# Ranger_I2C.net
KiCad netlist of a schematic drawn in EAGLE
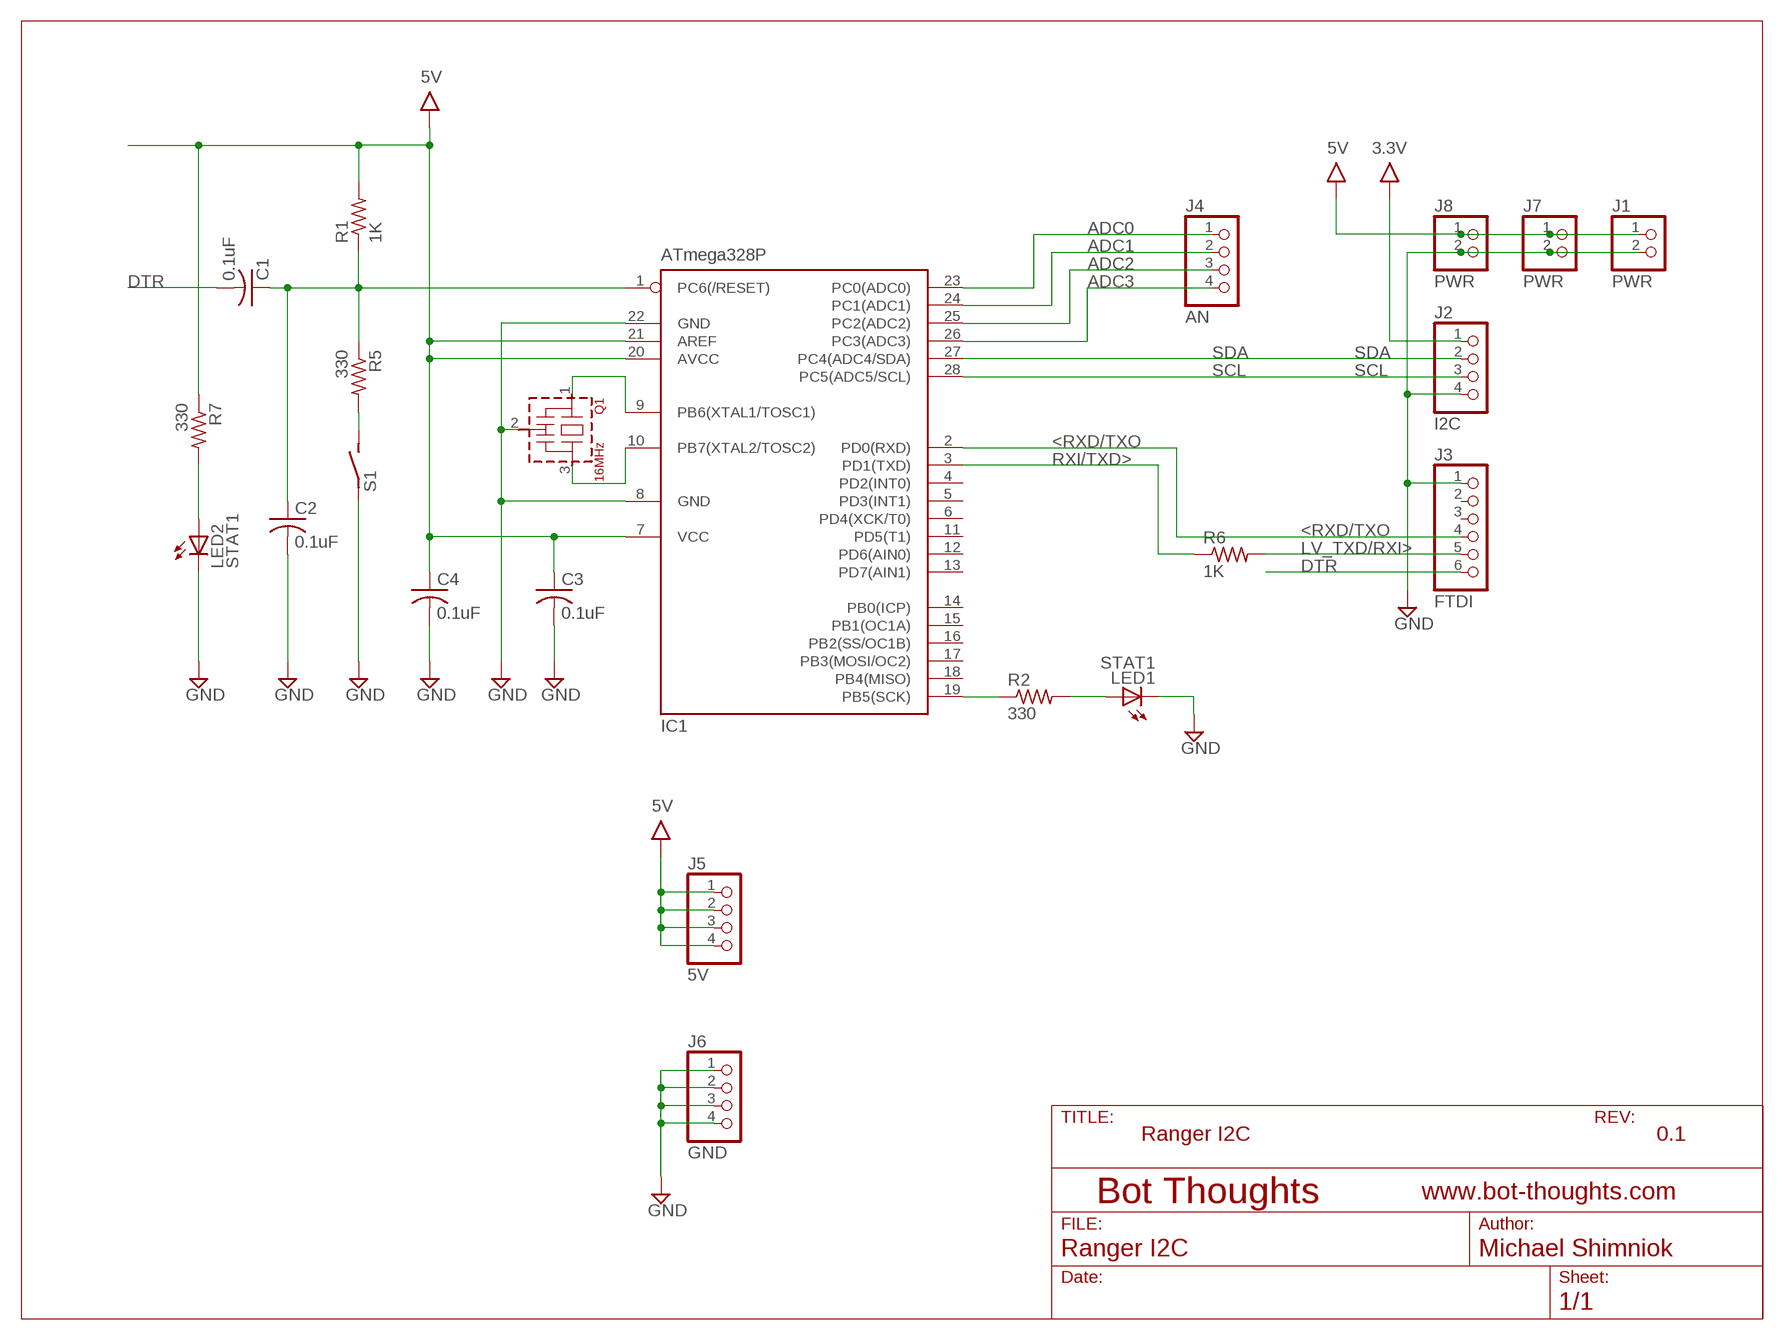
[diagram p0: schematic, sheet 1]

(export (version "E")
  (design (tool "Eeschema 10.0.6"))
  (components
    (comp (ref "C1")
      (value "0.1uF")
      (footprint "eagle-import:C050-025X075")
      (fields (field (name "PARTNO") "CC0603ZRY5V7BB104"))
      (libsource (lib "eagle-import") (part "C-US050-025X075"))
    )
    (comp (ref "C2")
      (value "0.1uF")
      (footprint "eagle-import:C050-025X075")
      (fields (field (name "PARTNO") "C1608X5R0J105K"))
      (libsource (lib "eagle-import") (part "C-US050-025X075"))
    )
    (comp (ref "C3")
      (value "0.1uF")
      (footprint "eagle-import:C050-025X075")
      (fields (field (name "PARTNO") "C1608X5R0J105K"))
      (libsource (lib "eagle-import") (part "C-US050-025X075"))
    )
    (comp (ref "C4")
      (value "0.1uF")
      (footprint "eagle-import:C050-025X075")
      (fields (field (name "PARTNO") "C1608X5R0J105K"))
      (libsource (lib "eagle-import") (part "C-US050-025X075"))
    )
    (comp (ref "IC1")
      (value "ATmega328P")
      (footprint "eagle-import:DIL28-3")
      (fields (field (name "PARTNO") "DEV-10524"))
      (libsource (lib "eagle-import") (part "MEGA8-P"))
    )
    (comp (ref "J1")
      (value "PWR")
      (footprint "eagle-import:1X02-S")
      (libsource (lib "eagle-import") (part "PINHD-1X02_2.54-S"))
    )
    (comp (ref "J2")
      (value "I2C")
      (footprint "eagle-import:1X04-S")
      (fields (field (name "PARTNO") "2211S-04G"))
      (libsource (lib "eagle-import") (part "PINHD-1X04_2.54-S"))
    )
    (comp (ref "J3")
      (value "FTDI")
      (footprint "eagle-import:1X06-S")
      (fields (field (name "PARTNO") "2211S-06G"))
      (libsource (lib "eagle-import") (part "PINHD-1X06_2.54-S"))
    )
    (comp (ref "J4")
      (value "AN")
      (footprint "eagle-import:1X04-S")
      (fields (field (name "PARTNO") "2211S-04G"))
      (libsource (lib "eagle-import") (part "PINHD-1X04_2.54-S"))
    )
    (comp (ref "J5")
      (value "5V")
      (footprint "eagle-import:1X04-S")
      (fields (field (name "PARTNO") "2211S-04G"))
      (libsource (lib "eagle-import") (part "PINHD-1X04_2.54-S"))
    )
    (comp (ref "J6")
      (value "GND")
      (footprint "eagle-import:1X04-S")
      (fields (field (name "PARTNO") "2211S-04G"))
      (libsource (lib "eagle-import") (part "PINHD-1X04_2.54-S"))
    )
    (comp (ref "J7")
      (value "PWR")
      (footprint "eagle-import:1X02-S")
      (libsource (lib "eagle-import") (part "PINHD-1X02_2.54-S"))
    )
    (comp (ref "J8")
      (value "PWR")
      (footprint "eagle-import:1X02-S")
      (libsource (lib "eagle-import") (part "PINHD-1X02_2.54-S"))
    )
    (comp (ref "LED1")
      (value "STAT1")
      (footprint "eagle-import:LED3MM")
      (libsource (lib "eagle-import") (part "LED3MM"))
    )
    (comp (ref "LED2")
      (value "STAT1")
      (footprint "eagle-import:LED3MM")
      (libsource (lib "eagle-import") (part "LED3MM"))
    )
    (comp (ref "Q1")
      (value "16MHz")
      (footprint "eagle-import:CSTLS_G9")
      (fields (field (name "PARTNO") "AWCR-16.00MD"))
      (libsource (lib "eagle-import") (part "murata-resonators_CSTLS_G"))
    )
    (comp (ref "R1")
      (value "1K")
      (footprint "eagle-import:0204_5")
      (libsource (lib "eagle-import") (part "R-US_0204/5"))
    )
    (comp (ref "R2")
      (value "330")
      (footprint "eagle-import:0204_5")
      (fields (field (name "PARTNO") "CRCW0603330RJNEA"))
      (libsource (lib "eagle-import") (part "R-US_0204/5"))
    )
    (comp (ref "R5")
      (value "330")
      (footprint "eagle-import:0204_5")
      (fields (field (name "PARTNO") "CRCW0603330RJNEA"))
      (libsource (lib "eagle-import") (part "R-US_0204/5"))
    )
    (comp (ref "R6")
      (value "1K")
      (footprint "eagle-import:0204_5")
      (fields (field (name "PARTNO") "CRCW0603330RJNEA"))
      (libsource (lib "eagle-import") (part "R-US_0204/5"))
    )
    (comp (ref "R7")
      (value "330")
      (footprint "eagle-import:0204_5")
      (fields (field (name "PARTNO") "CRCW0603330RJNEA"))
      (libsource (lib "eagle-import") (part "R-US_0204/5"))
    )
    (comp (ref "S1")
      (value "RESET\\")
      (footprint "eagle-import:EVQ11X09")
      (fields (field (name "PARTNO") "SALVAGE"))
      (libsource (lib "eagle-import") (part "SPST2EVQ11X09"))
    )
  )
  (nets
    (net (code "1") (name "/<RXD{slash}TXO") (class "Default")
      (node (ref "IC1") (pin "2") (pinfunction "PD0(RXD)_2") (pintype "bidirectional"))
      (node (ref "J3") (pin "4") (pinfunction "4_4") (pintype "passive"))
    )
    (net (code "2") (name "/ADC0") (class "Default")
      (node (ref "IC1") (pin "23") (pinfunction "PC0(ADC0)_23") (pintype "bidirectional"))
      (node (ref "J4") (pin "1") (pinfunction "1_1") (pintype "passive"))
    )
    (net (code "3") (name "/ADC1") (class "Default")
      (node (ref "IC1") (pin "24") (pinfunction "PC1(ADC1)_24") (pintype "bidirectional"))
      (node (ref "J4") (pin "2") (pinfunction "2_2") (pintype "passive"))
    )
    (net (code "4") (name "/ADC2") (class "Default")
      (node (ref "IC1") (pin "25") (pinfunction "PC2(ADC2)_25") (pintype "bidirectional"))
      (node (ref "J4") (pin "3") (pinfunction "3_3") (pintype "passive"))
    )
    (net (code "5") (name "/ADC3") (class "Default")
      (node (ref "IC1") (pin "26") (pinfunction "PC3(ADC3)_26") (pintype "bidirectional"))
      (node (ref "J4") (pin "4") (pinfunction "4_4") (pintype "passive"))
    )
    (net (code "6") (name "/DTR") (class "Default")
      (node (ref "C1") (pin "2") (pinfunction "2_2") (pintype "passive"))
      (node (ref "J3") (pin "6") (pinfunction "6_6") (pintype "passive"))
    )
    (net (code "7") (name "/LV_TXD{slash}RXI>") (class "Default")
      (node (ref "J3") (pin "5") (pinfunction "5_5") (pintype "passive"))
      (node (ref "R6") (pin "2") (pinfunction "2_2") (pintype "passive"))
    )
    (net (code "8") (name "/RXI{slash}TXD>") (class "Default")
      (node (ref "IC1") (pin "3") (pinfunction "PD1(TXD)_3") (pintype "bidirectional"))
      (node (ref "R6") (pin "1") (pinfunction "1_1") (pintype "passive"))
    )
    (net (code "9") (name "/SCL") (class "Default")
      (node (ref "IC1") (pin "28") (pinfunction "PC5(ADC5/SCL)_28") (pintype "bidirectional"))
      (node (ref "J2") (pin "3") (pinfunction "3_3") (pintype "passive"))
    )
    (net (code "10") (name "/SDA") (class "Default")
      (node (ref "IC1") (pin "27") (pinfunction "PC4(ADC4/SDA)_27") (pintype "bidirectional"))
      (node (ref "J2") (pin "2") (pinfunction "2_2") (pintype "passive"))
    )
    (net (code "11") (name "3.3V") (class "Default")
      (node (ref "J2") (pin "1") (pinfunction "1_1") (pintype "passive"))
    )
    (net (code "12") (name "5V") (class "Default")
      (node (ref "C3") (pin "1") (pinfunction "1_1") (pintype "passive"))
      (node (ref "C4") (pin "1") (pinfunction "1_1") (pintype "passive"))
      (node (ref "IC1") (pin "20") (pinfunction "AVCC_20") (pintype "power_in"))
      (node (ref "IC1") (pin "21") (pinfunction "AREF_21") (pintype "passive"))
      (node (ref "IC1") (pin "7") (pinfunction "VCC_7") (pintype "power_in"))
      (node (ref "J1") (pin "1") (pinfunction "1_1") (pintype "passive"))
      (node (ref "J5") (pin "1") (pinfunction "1_1") (pintype "passive"))
      (node (ref "J5") (pin "2") (pinfunction "2_2") (pintype "passive"))
      (node (ref "J5") (pin "3") (pinfunction "3_3") (pintype "passive"))
      (node (ref "J5") (pin "4") (pinfunction "4_4") (pintype "passive"))
      (node (ref "J7") (pin "1") (pinfunction "1_1") (pintype "passive"))
      (node (ref "J8") (pin "1") (pinfunction "1_1") (pintype "passive"))
      (node (ref "R1") (pin "2") (pinfunction "2_2") (pintype "passive"))
      (node (ref "R7") (pin "1") (pinfunction "1_1") (pintype "passive"))
    )
    (net (code "13") (name "GND") (class "Default")
      (node (ref "C2") (pin "2") (pinfunction "2_2") (pintype "passive"))
      (node (ref "C3") (pin "2") (pinfunction "2_2") (pintype "passive"))
      (node (ref "C4") (pin "2") (pinfunction "2_2") (pintype "passive"))
      (node (ref "IC1") (pin "22") (pinfunction "GND_22") (pintype "power_in"))
      (node (ref "IC1") (pin "8") (pinfunction "GND_8") (pintype "power_in"))
      (node (ref "J1") (pin "2") (pinfunction "2_2") (pintype "passive"))
      (node (ref "J2") (pin "4") (pinfunction "4_4") (pintype "passive"))
      (node (ref "J3") (pin "1") (pinfunction "1_1") (pintype "passive"))
      (node (ref "J6") (pin "1") (pinfunction "1_1") (pintype "passive"))
      (node (ref "J6") (pin "2") (pinfunction "2_2") (pintype "passive"))
      (node (ref "J6") (pin "3") (pinfunction "3_3") (pintype "passive"))
      (node (ref "J6") (pin "4") (pinfunction "4_4") (pintype "passive"))
      (node (ref "J7") (pin "2") (pinfunction "2_2") (pintype "passive"))
      (node (ref "J8") (pin "2") (pinfunction "2_2") (pintype "passive"))
      (node (ref "LED1") (pin "K") (pinfunction "C_K") (pintype "passive"))
      (node (ref "LED2") (pin "K") (pinfunction "C_K") (pintype "passive"))
      (node (ref "Q1") (pin "2") (pinfunction "VSS_2") (pintype "power_in"))
      (node (ref "S1") (pin "1") (pinfunction "1_1") (pintype "passive"))
    )
    (net (code "14") (name "Net-(IC1-PB5(SCK))") (class "Default")
      (node (ref "IC1") (pin "19") (pinfunction "PB5(SCK)_19") (pintype "bidirectional"))
      (node (ref "R2") (pin "1") (pinfunction "1_1") (pintype "passive"))
    )
    (net (code "15") (name "Net-(IC1-PB6(XTAL1{slash}TOSC1))") (class "Default")
      (node (ref "IC1") (pin "9") (pinfunction "PB6(XTAL1/TOSC1)_9") (pintype "bidirectional"))
      (node (ref "Q1") (pin "1") (pinfunction "1_1") (pintype "output"))
    )
    (net (code "16") (name "Net-(IC1-PB7(XTAL2{slash}TOSC2))") (class "Default")
      (node (ref "IC1") (pin "10") (pinfunction "PB7(XTAL2/TOSC2)_10") (pintype "bidirectional"))
      (node (ref "Q1") (pin "3") (pinfunction "3_3") (pintype "input"))
    )
    (net (code "17") (name "Net-(IC1-PC6({slash}RESET))") (class "Default")
      (node (ref "C1") (pin "1") (pinfunction "1_1") (pintype "passive"))
      (node (ref "C2") (pin "1") (pinfunction "1_1") (pintype "passive"))
      (node (ref "IC1") (pin "1") (pinfunction "PC6(/RESET)_1") (pintype "bidirectional"))
      (node (ref "R1") (pin "1") (pinfunction "1_1") (pintype "passive"))
      (node (ref "R5") (pin "1") (pinfunction "1_1") (pintype "passive"))
    )
    (net (code "18") (name "Net-(LED1-PadA)") (class "Default")
      (node (ref "LED1") (pin "A") (pinfunction "A_A") (pintype "passive"))
      (node (ref "R2") (pin "2") (pinfunction "2_2") (pintype "passive"))
    )
    (net (code "19") (name "Net-(LED2-PadA)") (class "Default")
      (node (ref "LED2") (pin "A") (pinfunction "A_A") (pintype "passive"))
      (node (ref "R7") (pin "2") (pinfunction "2_2") (pintype "passive"))
    )
    (net (code "20") (name "Net-(R5-Pad2)") (class "Default")
      (node (ref "R5") (pin "2") (pinfunction "2_2") (pintype "passive"))
      (node (ref "S1") (pin "2") (pinfunction "2_2") (pintype "passive"))
    )
    (net (code "21") (name "unconnected-(IC1-PB0(ICP)-Pad14)") (class "Default")
      (node (ref "IC1") (pin "14") (pinfunction "PB0(ICP)_14") (pintype "bidirectional"))
    )
    (net (code "22") (name "unconnected-(IC1-PB1(OC1A)-Pad15)") (class "Default")
      (node (ref "IC1") (pin "15") (pinfunction "PB1(OC1A)_15") (pintype "bidirectional"))
    )
    (net (code "23") (name "unconnected-(IC1-PB2(SS{slash}OC1B)-Pad16)") (class "Default")
      (node (ref "IC1") (pin "16") (pinfunction "PB2(SS/OC1B)_16") (pintype "bidirectional"))
    )
    (net (code "24") (name "unconnected-(IC1-PB3(MOSI{slash}OC2)-Pad17)") (class "Default")
      (node (ref "IC1") (pin "17") (pinfunction "PB3(MOSI/OC2)_17") (pintype "bidirectional"))
    )
    (net (code "25") (name "unconnected-(IC1-PB4(MISO)-Pad18)") (class "Default")
      (node (ref "IC1") (pin "18") (pinfunction "PB4(MISO)_18") (pintype "bidirectional"))
    )
    (net (code "26") (name "unconnected-(IC1-PD2(INT0)-Pad4)") (class "Default")
      (node (ref "IC1") (pin "4") (pinfunction "PD2(INT0)_4") (pintype "bidirectional"))
    )
    (net (code "27") (name "unconnected-(IC1-PD3(INT1)-Pad5)") (class "Default")
      (node (ref "IC1") (pin "5") (pinfunction "PD3(INT1)_5") (pintype "bidirectional"))
    )
    (net (code "28") (name "unconnected-(IC1-PD4(XCK{slash}T0)-Pad6)") (class "Default")
      (node (ref "IC1") (pin "6") (pinfunction "PD4(XCK/T0)_6") (pintype "bidirectional"))
    )
    (net (code "29") (name "unconnected-(IC1-PD5(T1)-Pad11)") (class "Default")
      (node (ref "IC1") (pin "11") (pinfunction "PD5(T1)_11") (pintype "bidirectional"))
    )
    (net (code "30") (name "unconnected-(IC1-PD6(AIN0)-Pad12)") (class "Default")
      (node (ref "IC1") (pin "12") (pinfunction "PD6(AIN0)_12") (pintype "bidirectional"))
    )
    (net (code "31") (name "unconnected-(IC1-PD7(AIN1)-Pad13)") (class "Default")
      (node (ref "IC1") (pin "13") (pinfunction "PD7(AIN1)_13") (pintype "bidirectional"))
    )
    (net (code "32") (name "unconnected-(J3-Pad2)") (class "Default")
      (node (ref "J3") (pin "2") (pinfunction "2_2") (pintype "passive"))
    )
    (net (code "33") (name "unconnected-(J3-Pad3)") (class "Default")
      (node (ref "J3") (pin "3") (pinfunction "3_3") (pintype "passive"))
    )
  )
)
